# Adafruit_MCP9600.net
KiCad netlist of a schematic drawn in Altium Designer
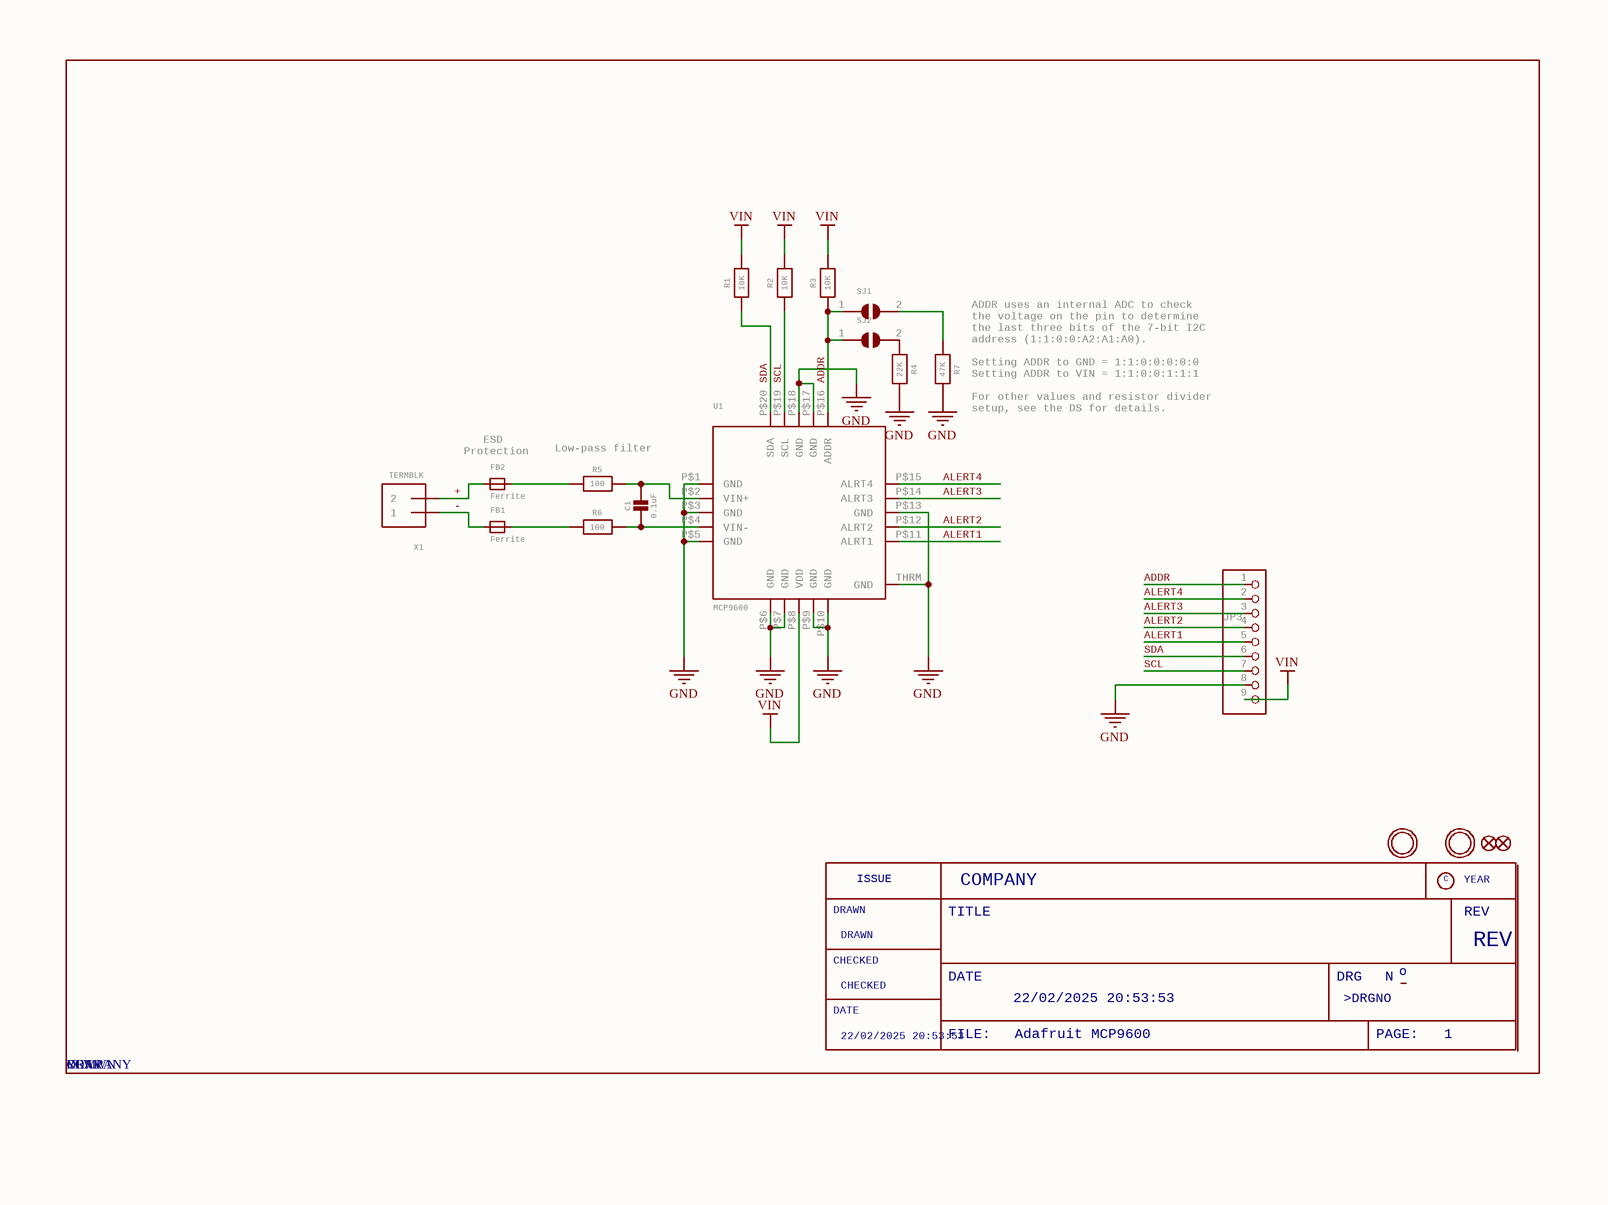
[diagram p0: Adafruit MCP9600.SchDoc]

(export (version "E")
  (design (tool "Eeschema 10.0.6"))
  (components
    (comp (ref "C1")
      (value "0.1uF")
      (footprint "0603-NO")
      (libsource (lib "microbuilder") (part "CAP_CERAMIC0603_NO"))
    )
    (comp (ref "FB1")
      (value "Ferrite")
      (footprint "0805-NO")
      (libsource (lib "microbuilder") (part "FERRITE-0805NO"))
    )
    (comp (ref "FB2")
      (value "Ferrite")
      (footprint "0805-NO")
      (libsource (lib "microbuilder") (part "FERRITE-0805NO"))
    )
    (comp (ref "FID1")
      (value "FIDUCIAL_1MM")
      (footprint "FIDUCIAL_1MM")
      (description "Fiducial Alignment Points   Various fiducial points for machine vision alignment.")
      (libsource (lib "microbuilder") (part "FIDUCIAL_1MM"))
    )
    (comp (ref "FID2")
      (value "FIDUCIAL_1MM")
      (footprint "FIDUCIAL_1MM")
      (description "Fiducial Alignment Points   Various fiducial points for machine vision alignment.")
      (libsource (lib "microbuilder") (part "FIDUCIAL_1MM"))
    )
    (comp (ref "JP3")
      (value "HEADER-1X970MIL")
      (footprint "1X09_ROUND_70")
      (description "PIN HEADER")
      (libsource (lib "microbuilder") (part "HEADER-1X970MIL"))
    )
    (comp (ref "R1")
      (value "10K")
      (footprint "0603-NO")
      (libsource (lib "microbuilder") (part "RESISTOR_0603_NOOUT"))
    )
    (comp (ref "R2")
      (value "10K")
      (footprint "0603-NO")
      (libsource (lib "microbuilder") (part "RESISTOR_0603_NOOUT"))
    )
    (comp (ref "R3")
      (value "10K")
      (footprint "0603-NO")
      (libsource (lib "microbuilder") (part "RESISTOR_0603_NOOUT"))
    )
    (comp (ref "R4")
      (value "22K")
      (footprint "0603-NO")
      (libsource (lib "microbuilder") (part "RESISTOR_0603_NOOUT"))
    )
    (comp (ref "R5")
      (value "100")
      (footprint "0603-NO")
      (libsource (lib "microbuilder") (part "RESISTOR_0603_NOOUT"))
    )
    (comp (ref "R6")
      (value "100")
      (footprint "0603-NO")
      (libsource (lib "microbuilder") (part "RESISTOR_0603_NOOUT"))
    )
    (comp (ref "R7")
      (value "47K")
      (footprint "0603-NO")
      (libsource (lib "microbuilder") (part "RESISTOR_0603_NOOUT"))
    )
    (comp (ref "SJ1")
      (value "SOLDERJUMPER")
      (footprint "SOLDERJUMPER_ARROW_NOPASTE")
      (libsource (lib "microbuilder") (part "SOLDERJUMPER"))
    )
    (comp (ref "SJ2")
      (value "SOLDERJUMPER")
      (footprint "SOLDERJUMPER_ARROW_NOPASTE")
      (libsource (lib "microbuilder") (part "SOLDERJUMPER"))
    )
    (comp (ref "U$1")
      (value "MOUNTINGHOLE2.5")
      (footprint "MOUNTINGHOLE_2.5_PLATED")
      (description "Mounting Hole   For #2 screws (0.086\"/2.18mm width, 0.094\"/2.4mm hole) use 2.5mm")
      (libsource (lib "microbuilder") (part "MOUNTINGHOLE2.5"))
    )
    (comp (ref "U$3")
      (value "MOUNTINGHOLE2.5")
      (footprint "MOUNTINGHOLE_2.5_PLATED")
      (description "Mounting Hole   For #2 screws (0.086\"/2.18mm width, 0.094\"/2.4mm hole) use 2.5mm")
      (libsource (lib "microbuilder") (part "MOUNTINGHOLE2.5"))
    )
    (comp (ref "U1")
      (value "MCP9600")
      (footprint "VQFN20_5MM")
      (description "MCP9600 -  I2C Thermocouple EMF to Temperature Converter Operating Voltage Range: 2.7V to 5.5V")
      (libsource (lib "microbuilder") (part "MCP9600"))
    )
    (comp (ref "X1")
      (value "TERMBLK")
      (footprint "TERMBLOCK_1X2-3.5MM")
      (description "3.5mm Terminal block    http://www.ladyada.net/library/pcb/eaglelibrary.html")
      (libsource (lib "microbuilder") (part "TERMBLOCK_1X2_3.5MM"))
    )
  )
  (nets
    (net (code "1") (name "/+") (class "Default")
      (node (ref "FB2") (pin "1") (pinfunction "P$1_1") (pintype "passive"))
      (node (ref "X1") (pin "2") (pinfunction "2_2") (pintype "passive"))
    )
    (net (code "2") (name "/-") (class "Default")
      (node (ref "FB1") (pin "1") (pinfunction "P$1_1") (pintype "passive"))
      (node (ref "X1") (pin "1") (pinfunction "1_1") (pintype "passive"))
    )
    (net (code "3") (name "/ADDR") (class "Default")
      (node (ref "JP3") (pin "1") (pinfunction "1_1") (pintype "passive"))
      (node (ref "R3") (pin "1") (pinfunction "1_1") (pintype "passive"))
      (node (ref "SJ1") (pin "1") (pinfunction "1_1") (pintype "passive"))
      (node (ref "SJ2") (pin "1") (pinfunction "1_1") (pintype "passive"))
      (node (ref "U1") (pin "P$16") (pinfunction "ADDR_P$16") (pintype "bidirectional"))
    )
    (net (code "4") (name "/ALERT1") (class "Default")
      (node (ref "JP3") (pin "5") (pinfunction "5_5") (pintype "passive"))
      (node (ref "U1") (pin "P$11") (pinfunction "ALRT1_P$11") (pintype "bidirectional"))
    )
    (net (code "5") (name "/ALERT2") (class "Default")
      (node (ref "JP3") (pin "4") (pinfunction "4_4") (pintype "passive"))
      (node (ref "U1") (pin "P$12") (pinfunction "ALRT2_P$12") (pintype "bidirectional"))
    )
    (net (code "6") (name "/ALERT3") (class "Default")
      (node (ref "JP3") (pin "3") (pinfunction "3_3") (pintype "passive"))
      (node (ref "U1") (pin "P$14") (pinfunction "ALRT3_P$14") (pintype "bidirectional"))
    )
    (net (code "7") (name "/ALERT4") (class "Default")
      (node (ref "JP3") (pin "2") (pinfunction "2_2") (pintype "passive"))
      (node (ref "U1") (pin "P$15") (pinfunction "ALRT4_P$15") (pintype "bidirectional"))
    )
    (net (code "8") (name "/SCL") (class "Default")
      (node (ref "JP3") (pin "7") (pinfunction "7_7") (pintype "passive"))
      (node (ref "R2") (pin "1") (pinfunction "1_1") (pintype "passive"))
      (node (ref "U1") (pin "P$19") (pinfunction "SCL_P$19") (pintype "bidirectional"))
    )
    (net (code "9") (name "/SDA") (class "Default")
      (node (ref "JP3") (pin "6") (pinfunction "6_6") (pintype "passive"))
      (node (ref "R1") (pin "1") (pinfunction "1_1") (pintype "passive"))
      (node (ref "U1") (pin "P$20") (pinfunction "SDA_P$20") (pintype "bidirectional"))
    )
    (net (code "10") (name "GND") (class "Default")
      (node (ref "JP3") (pin "8") (pinfunction "8_8") (pintype "passive"))
      (node (ref "R4") (pin "2") (pinfunction "2_2") (pintype "passive"))
      (node (ref "R7") (pin "2") (pinfunction "2_2") (pintype "passive"))
      (node (ref "U1") (pin "P$1") (pinfunction "GND_P$1") (pintype "bidirectional"))
      (node (ref "U1") (pin "P$10") (pinfunction "GND_P$10") (pintype "bidirectional"))
      (node (ref "U1") (pin "P$13") (pinfunction "GND_P$13") (pintype "bidirectional"))
      (node (ref "U1") (pin "P$17") (pinfunction "GND_P$17") (pintype "bidirectional"))
      (node (ref "U1") (pin "P$18") (pinfunction "GND_P$18") (pintype "bidirectional"))
      (node (ref "U1") (pin "P$3") (pinfunction "GND_P$3") (pintype "bidirectional"))
      (node (ref "U1") (pin "P$5") (pinfunction "GND_P$5") (pintype "bidirectional"))
      (node (ref "U1") (pin "P$6") (pinfunction "GND_P$6") (pintype "bidirectional"))
      (node (ref "U1") (pin "P$7") (pinfunction "GND_P$7") (pintype "bidirectional"))
      (node (ref "U1") (pin "P$9") (pinfunction "GND_P$9") (pintype "bidirectional"))
      (node (ref "U1") (pin "THRM") (pinfunction "GND_THRM") (pintype "bidirectional"))
    )
    (net (code "11") (name "Net-(FB1-P$2)") (class "Default")
      (node (ref "FB1") (pin "2") (pinfunction "P$2_2") (pintype "passive"))
      (node (ref "R6") (pin "1") (pinfunction "1_1") (pintype "passive"))
    )
    (net (code "12") (name "Net-(FB2-P$2)") (class "Default")
      (node (ref "FB2") (pin "2") (pinfunction "P$2_2") (pintype "passive"))
      (node (ref "R5") (pin "1") (pinfunction "1_1") (pintype "passive"))
    )
    (net (code "13") (name "Net-(R4-Pad1)") (class "Default")
      (node (ref "R4") (pin "1") (pinfunction "1_1") (pintype "passive"))
      (node (ref "SJ2") (pin "2") (pinfunction "2_2") (pintype "passive"))
    )
    (net (code "14") (name "Net-(R7-Pad1)") (class "Default")
      (node (ref "R7") (pin "1") (pinfunction "1_1") (pintype "passive"))
      (node (ref "SJ1") (pin "2") (pinfunction "2_2") (pintype "passive"))
    )
    (net (code "15") (name "Net-(U1-VIN+)") (class "Default")
      (node (ref "C1") (pin "1") (pinfunction "1_1") (pintype "passive"))
      (node (ref "R5") (pin "2") (pinfunction "2_2") (pintype "passive"))
      (node (ref "U1") (pin "P$2") (pinfunction "VIN+_P$2") (pintype "bidirectional"))
    )
    (net (code "16") (name "Net-(U1-VIN-)") (class "Default")
      (node (ref "C1") (pin "2") (pinfunction "2_2") (pintype "passive"))
      (node (ref "R6") (pin "2") (pinfunction "2_2") (pintype "passive"))
      (node (ref "U1") (pin "P$4") (pinfunction "VIN-_P$4") (pintype "bidirectional"))
    )
    (net (code "17") (name "VIN") (class "Default")
      (node (ref "JP3") (pin "9") (pinfunction "9_9") (pintype "passive"))
      (node (ref "R1") (pin "2") (pinfunction "2_2") (pintype "passive"))
      (node (ref "R2") (pin "2") (pinfunction "2_2") (pintype "passive"))
      (node (ref "R3") (pin "2") (pinfunction "2_2") (pintype "passive"))
      (node (ref "U1") (pin "P$8") (pinfunction "VDD_P$8") (pintype "bidirectional"))
    )
  )
)
